# Power_Board.net
KiCad netlist of a schematic drawn in Altium Designer
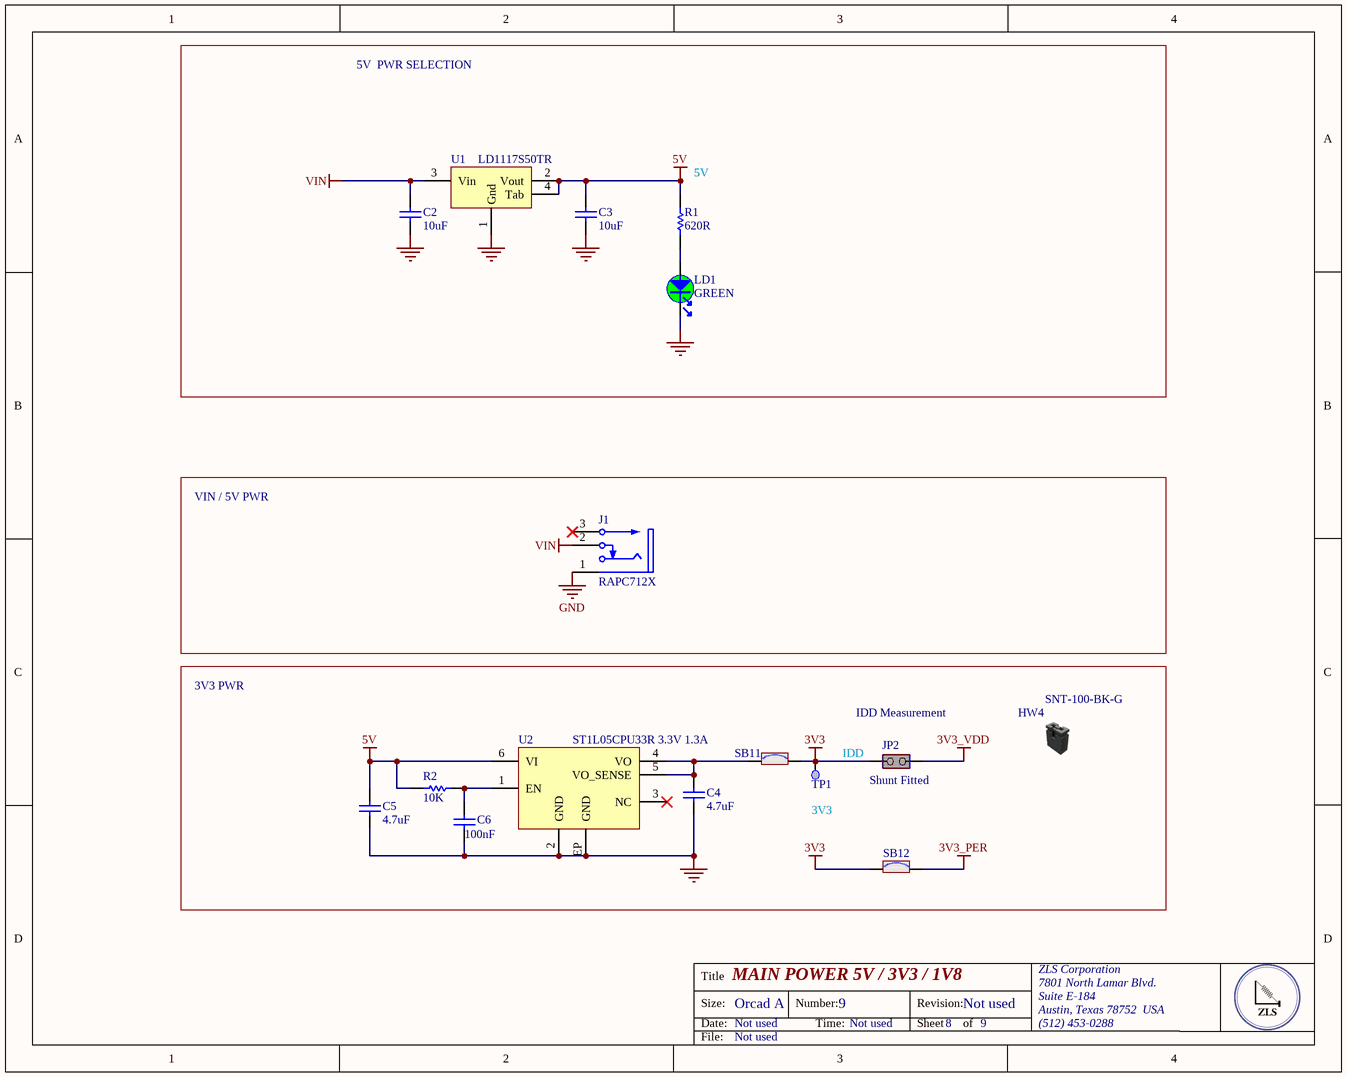
[diagram p0: Power_Board.SchDoc]

(export (version "E")
  (design (tool "Eeschema 10.0.6"))
  (components
    (comp (ref "C2")
      (value "10uF")
      (footprint "C0805")
      (description "Capacitor, MLCC, 10uF, 25V, X5R, 10%, 0805, T=0,85mm")
      (fields
        (field (name "INTERNAL_PART_NUMBER") "MCD-00014")
        (field (name "MANUFACTURER_PART_NUMBER") "CC0805KRX5R8BB106")
        (field (name "PROVIDED_BY") "SUBCO")
      )
      (libsource (lib "MCD_PARTS_database") (part "Capacitor"))
    )
    (comp (ref "C3")
      (value "10uF")
      (footprint "C0805")
      (description "Capacitor, MLCC, 10uF, 25V, X5R, 10%, 0805, T=0,85mm")
      (fields
        (field (name "INTERNAL_PART_NUMBER") "MCD-00014")
        (field (name "MANUFACTURER_PART_NUMBER") "CC0805KRX5R8BB106")
        (field (name "PROVIDED_BY") "SUBCO")
      )
      (libsource (lib "MCD_PARTS_database") (part "Capacitor"))
    )
    (comp (ref "C4")
      (value "4.7uF")
      (footprint "C0603")
      (description "Capacitor, MLCC, 4.7µF, 10V, X5R, 20%, 0603, T=0,8mm")
      (fields
        (field (name "INTERNAL_PART_NUMBER") "MCD-01121")
        (field (name "MANUFACTURER_PART_NUMBER") "GRM188R61A475ME15")
        (field (name "PROVIDED_BY") "SUBCO")
      )
      (libsource (lib "MCD_PARTS_database") (part "Capacitor"))
    )
    (comp (ref "C5")
      (value "4.7uF")
      (footprint "C0603")
      (description "Capacitor, MLCC, 4.7uF, 16V, X5R, 20%, 0603, T=0,8mm")
      (fields
        (field (name "INTERNAL_PART_NUMBER") "MCD-00097")
        (field (name "MANUFACTURER_PART_NUMBER") "GRM188R61C475KE11")
        (field (name "PROVIDED_BY") "SUBCO")
      )
      (libsource (lib "MCD_PARTS_database") (part "Capacitor"))
    )
    (comp (ref "C6")
      (value "Capacitor")
      (footprint "C0402")
      (description "CAP CER 0.1UF 16V X7R 0402")
      (fields
        (field (name "MANUFACTURER") "Yageo")
        (field (name "MANUFACTURER PART NUMBER") "CC0402KRX7R7BB104")
        (field (name "CAPACITANCE") "100nF")
      )
      (libsource (lib "MCD_PARTS_database") (part "Capacitor"))
    )
    (comp (ref "HW4")
      (value "SNT-100-BK-G")
      (description "SHUNT 2.54mm BLACK")
      (fields
        (field (name "INTERNAL_PART_NUMBER") "MCD-00043")
        (field (name "MANUFACTURER") "SAMTEC")
        (field (name "PROVIDED_BY") "SUBCO")
      )
      (libsource (lib "MCD_PARTS_database") (part "Shunt Black 2.54mm"))
    )
    (comp (ref "J1")
      (value "RAPC712X")
      (footprint "SWITCH-RAPC712X-3_V")
      (description "Conn Powerjack Mini R/A PCMT, 5 A, 3-Pin THD, RoHS")
      (fields (field (name "MANUFACTURER") "Switchcraft"))
      (libsource (lib "Altium Content Vault") (part "SWITCH-RAPC712X-3"))
    )
    (comp (ref "JP2")
      (value "Shunt Fitted")
      (footprint "CON_SAMTEC_TSW-102-07-G-S")
      (description "Header, 2x1, 2,54mm, VR, TH, Height 5.84mm/2.54mm - Shunt Fitted by default")
      (fields
        (field (name "INTERNAL_PART_NUMBER") "MCD-00683")
        (field (name "MANUFACTURER_PART_NUMBER") "TSW-102-07-x-S")
        (field (name "PROVIDED_BY") "SUBCO")
      )
      (libsource (lib "MCD_PARTS_database") (part "Jumper_Header 2x1 Fitted"))
    )
    (comp (ref "LD1")
      (value "GREEN")
      (footprint "LED_0603_OSRAM_LG-Q396-PS-35_GREEN_1A2K_H0P4")
      (description "LED Green, 0603 SMD, Forward Voltage Typ=2V, Max=2.5V")
      (fields
        (field (name "INTERNAL_PART_NUMBER") "MCD-00588")
        (field (name "MANUFACTURER_PART_NUMBER") "LG Q396-PS-35")
        (field (name "PROVIDED_BY") "SUBCO")
      )
      (libsource (lib "MCD_PARTS_database") (part "LED_green"))
    )
    (comp (ref "R1")
      (value "620R")
      (footprint "R0603")
      (description "Resistor,620R,0603,1%,1/10W")
      (fields
        (field (name "INTERNAL_PART_NUMBER") "MCD-00500")
        (field (name "MANUFACTURER_PART_NUMBER") "RC0603FR-07620RL")
        (field (name "PROVIDED_BY") "SUBCO")
      )
      (libsource (lib "MCD_PARTS_database") (part "Resistor"))
    )
    (comp (ref "R2")
      (value "10K")
      (footprint "R0402")
      (description "Resistor,10K,0402,1%,1/16W")
      (fields
        (field (name "INTERNAL_PART_NUMBER") "MCD-00053")
        (field (name "MANUFACTURER_PART_NUMBER") "RC0402FR-0710KL")
        (field (name "PROVIDED_BY") "SUBCO")
      )
      (libsource (lib "MCD_PARTS_database") (part "Resistor"))
    )
    (comp (ref "SB11")
      (value "SB_ON")
      (footprint "SOLDER-BRIDGE_R0603-0R")
      (description "Solder Bridge ON")
      (fields
        (field (name "INTERNAL_PART_NUMBER") "MCD-00071")
        (field (name "MANUFACTURER_PART_NUMBER") "RC0603JR-070RL")
        (field (name "PROVIDED_BY") "SUBCO")
      )
      (libsource (lib "MCD_PARTS_database") (part "SB_ON"))
    )
    (comp (ref "SB12")
      (value "SB_ON")
      (footprint "SOLDER-BRIDGE_R0603-0R")
      (description "Solder Bridge ON")
      (fields
        (field (name "INTERNAL_PART_NUMBER") "MCD-00071")
        (field (name "MANUFACTURER_PART_NUMBER") "RC0603JR-070RL")
        (field (name "PROVIDED_BY") "SUBCO")
      )
      (libsource (lib "MCD_PARTS_database") (part "SB_ON"))
    )
    (comp (ref "TP1")
      (value "Test Point")
      (footprint "TP_SMD_1MM")
      (description "Test Point 1mm")
      (fields (field (name "INTERNAL_PART_NUMBER") "MCD-00074") (field (name "MANUFACTURER") "n/a"))
      (libsource (lib "MCD_PARTS_database") (part "Test Point"))
    )
    (comp (ref "U1")
      (value "LD1117S50TR")
      (footprint "REG_SOT223-TAB")
      (description "IC REG LDO 5V 0.8A SOT223")
      (fields
        (field (name "INTERNAL_PART_NUMBER") "MCD-00088")
        (field (name "MANUFACTURER") "STMICROELECTRONICS")
        (field (name "PROVIDED_BY") "SUBCO with ST control")
      )
      (libsource (lib "MCD_PARTS_database") (part "LD1117S50TR"))
    )
    (comp (ref "U2")
      (value "ST1L05CPU33R 3.3V 1.3A")
      (footprint "ICC_DFN6-EPAD_3X3_P095")
      (description "LDO, 3.3V, 1.3A, Very low quiescent current BiCMOS voltage regulator")
      (fields
        (field (name "INTERNAL_PART_NUMBER") "MCD-01025")
        (field (name "MANUFACTURER_PART_NUMBER") "ST1L05CPU33R")
        (field (name "PROVIDED_BY") "SUBCO with ST control")
      )
      (libsource (lib "MCD_PARTS_database") (part "ST1L05CPU33R"))
    )
  )
  (nets
    (net (code "1") (name "3V3") (class "Default")
      (node (ref "JP2") (pin "1") (pinfunction "COMMON_1") (pintype "passive"))
      (node (ref "SB11") (pin "2") (pinfunction "2_2") (pintype "passive"))
      (node (ref "SB12") (pin "1") (pinfunction "1_1") (pintype "passive"))
      (node (ref "TP1") (pin "1") (pinfunction "1_1") (pintype "passive"))
    )
    (net (code "2") (name "3V3_PER") (class "Default")
      (node (ref "SB12") (pin "2") (pinfunction "2_2") (pintype "passive"))
    )
    (net (code "3") (name "3V3_VDD") (class "Default")
      (node (ref "JP2") (pin "2") (pinfunction "NO_2") (pintype "passive"))
    )
    (net (code "4") (name "5V") (class "Default")
      (node (ref "C3") (pin "2") (pinfunction "2_2") (pintype "passive"))
      (node (ref "C5") (pin "2") (pinfunction "2_2") (pintype "passive"))
      (node (ref "R1") (pin "2") (pinfunction "2_2") (pintype "passive"))
      (node (ref "R2") (pin "2") (pinfunction "2_2") (pintype "passive"))
      (node (ref "U1") (pin "2") (pinfunction "Vout_2") (pintype "passive"))
      (node (ref "U1") (pin "4") (pinfunction "Tab_4") (pintype "passive"))
      (node (ref "U2") (pin "6") (pinfunction "VI_6") (pintype "passive"))
    )
    (net (code "5") (name "GND") (class "Default")
      (node (ref "C2") (pin "1") (pinfunction "1_1") (pintype "passive"))
      (node (ref "C3") (pin "1") (pinfunction "1_1") (pintype "passive"))
      (node (ref "C4") (pin "1") (pinfunction "1_1") (pintype "passive"))
      (node (ref "C5") (pin "1") (pinfunction "1_1") (pintype "passive"))
      (node (ref "C6") (pin "1") (pinfunction "1_1") (pintype "passive"))
      (node (ref "J1") (pin "1") (pinfunction "1_1") (pintype "passive"))
      (node (ref "LD1") (pin "2") (pintype "passive"))
      (node (ref "U1") (pin "1") (pinfunction "Gnd_1") (pintype "passive"))
      (node (ref "U2") (pin "2") (pinfunction "GND_2") (pintype "passive"))
      (node (ref "U2") (pin "EP") (pinfunction "GND_EP") (pintype "passive"))
    )
    (net (code "6") (name "Net-(LD1-Pad1)") (class "Default")
      (node (ref "LD1") (pin "1") (pintype "passive"))
      (node (ref "R1") (pin "1") (pinfunction "1_1") (pintype "passive"))
    )
    (net (code "7") (name "Net-(U2-EN)") (class "Default")
      (node (ref "C6") (pin "2") (pinfunction "2_2") (pintype "passive"))
      (node (ref "R2") (pin "1") (pinfunction "1_1") (pintype "passive"))
      (node (ref "U2") (pin "1") (pinfunction "EN_1") (pintype "passive"))
    )
    (net (code "8") (name "Net-(U2-VO)") (class "Default")
      (node (ref "C4") (pin "2") (pinfunction "2_2") (pintype "passive"))
      (node (ref "SB11") (pin "1") (pinfunction "1_1") (pintype "passive"))
      (node (ref "U2") (pin "4") (pinfunction "VO_4") (pintype "passive"))
      (node (ref "U2") (pin "5") (pinfunction "VO_SENSE_5") (pintype "passive"))
    )
    (net (code "9") (name "VIN") (class "Default")
      (node (ref "C2") (pin "2") (pinfunction "2_2") (pintype "passive"))
      (node (ref "J1") (pin "2") (pinfunction "2_2") (pintype "passive"))
      (node (ref "U1") (pin "3") (pinfunction "Vin_3") (pintype "passive"))
    )
    (net (code "10") (name "unconnected-(J1-Pad3)") (class "Default")
      (node (ref "J1") (pin "3") (pinfunction "3_3") (pintype "passive+no_connect"))
    )
    (net (code "11") (name "unconnected-(U2-NC-Pad3)") (class "Default")
      (node (ref "U2") (pin "3") (pinfunction "NC_3") (pintype "passive+no_connect"))
    )
  )
)
